# 40_Pin_Connector.net
KiCad netlist of a schematic drawn in Altium Designer
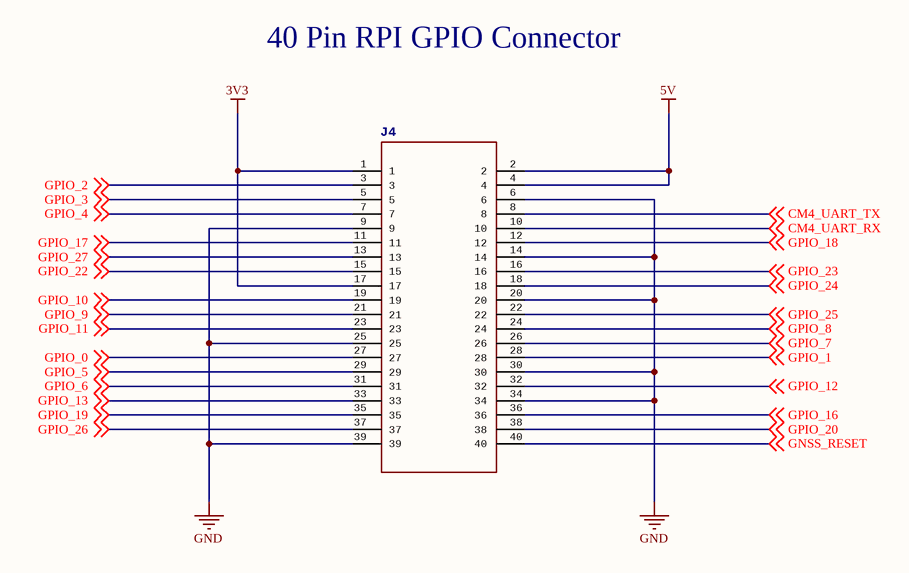
[diagram p0: 40_Pin_Connector.SchDoc]

(export (version "E")
  (design (tool "Eeschema 10.0.6"))
  (components
    (comp (ref "J4")
      (value "SAMTEC-A-HTSW-120-08-F-DJ")
      (footprint "SAMTEC-A-HTSW-120-08-F-D")
      (libsource (lib "SAMTEC-A-HTSW-120-08-F-D") (part "SAMTEC-A-HTSW-120-08-F-DJ"))
    )
  )
  (nets
    (net (code "1") (name "3V3") (class "Default")
      (node (ref "J4") (pin "1") (pinfunction "1_1") (pintype "passive"))
      (node (ref "J4") (pin "17") (pinfunction "17_17") (pintype "passive"))
    )
    (net (code "2") (name "5V") (class "Default")
      (node (ref "J4") (pin "2") (pinfunction "2_2") (pintype "passive"))
      (node (ref "J4") (pin "4") (pinfunction "4_4") (pintype "passive"))
    )
    (net (code "3") (name "CM4_UART_RX") (class "Default")
      (node (ref "J4") (pin "10") (pinfunction "10_10") (pintype "passive"))
    )
    (net (code "4") (name "CM4_UART_TX") (class "Default")
      (node (ref "J4") (pin "8") (pinfunction "8_8") (pintype "passive"))
    )
    (net (code "5") (name "GND") (class "Default")
      (node (ref "J4") (pin "14") (pinfunction "14_14") (pintype "passive"))
      (node (ref "J4") (pin "20") (pinfunction "20_20") (pintype "passive"))
      (node (ref "J4") (pin "25") (pinfunction "25_25") (pintype "passive"))
      (node (ref "J4") (pin "30") (pinfunction "30_30") (pintype "passive"))
      (node (ref "J4") (pin "34") (pinfunction "34_34") (pintype "passive"))
      (node (ref "J4") (pin "39") (pinfunction "39_39") (pintype "passive"))
      (node (ref "J4") (pin "6") (pinfunction "6_6") (pintype "passive"))
      (node (ref "J4") (pin "9") (pinfunction "9_9") (pintype "passive"))
    )
    (net (code "6") (name "GNSS_RESET") (class "Default")
      (node (ref "J4") (pin "40") (pinfunction "40_40") (pintype "passive"))
    )
    (net (code "7") (name "GPIO_0") (class "Default")
      (node (ref "J4") (pin "27") (pinfunction "27_27") (pintype "passive"))
    )
    (net (code "8") (name "GPIO_1") (class "Default")
      (node (ref "J4") (pin "28") (pinfunction "28_28") (pintype "passive"))
    )
    (net (code "9") (name "GPIO_2") (class "Default")
      (node (ref "J4") (pin "3") (pinfunction "3_3") (pintype "passive"))
    )
    (net (code "10") (name "GPIO_3") (class "Default")
      (node (ref "J4") (pin "5") (pinfunction "5_5") (pintype "passive"))
    )
    (net (code "11") (name "GPIO_4") (class "Default")
      (node (ref "J4") (pin "7") (pinfunction "7_7") (pintype "passive"))
    )
    (net (code "12") (name "GPIO_5") (class "Default")
      (node (ref "J4") (pin "29") (pinfunction "29_29") (pintype "passive"))
    )
    (net (code "13") (name "GPIO_6") (class "Default")
      (node (ref "J4") (pin "31") (pinfunction "31_31") (pintype "passive"))
    )
    (net (code "14") (name "GPIO_7") (class "Default")
      (node (ref "J4") (pin "26") (pinfunction "26_26") (pintype "passive"))
    )
    (net (code "15") (name "GPIO_8") (class "Default")
      (node (ref "J4") (pin "24") (pinfunction "24_24") (pintype "passive"))
    )
    (net (code "16") (name "GPIO_9") (class "Default")
      (node (ref "J4") (pin "21") (pinfunction "21_21") (pintype "passive"))
    )
    (net (code "17") (name "GPIO_10") (class "Default")
      (node (ref "J4") (pin "19") (pinfunction "19_19") (pintype "passive"))
    )
    (net (code "18") (name "GPIO_11") (class "Default")
      (node (ref "J4") (pin "23") (pinfunction "23_23") (pintype "passive"))
    )
    (net (code "19") (name "GPIO_12") (class "Default")
      (node (ref "J4") (pin "32") (pinfunction "32_32") (pintype "passive"))
    )
    (net (code "20") (name "GPIO_13") (class "Default")
      (node (ref "J4") (pin "33") (pinfunction "33_33") (pintype "passive"))
    )
    (net (code "21") (name "GPIO_16") (class "Default")
      (node (ref "J4") (pin "36") (pinfunction "36_36") (pintype "passive"))
    )
    (net (code "22") (name "GPIO_17") (class "Default")
      (node (ref "J4") (pin "11") (pinfunction "11_11") (pintype "passive"))
    )
    (net (code "23") (name "GPIO_18") (class "Default")
      (node (ref "J4") (pin "12") (pinfunction "12_12") (pintype "passive"))
    )
    (net (code "24") (name "GPIO_19") (class "Default")
      (node (ref "J4") (pin "35") (pinfunction "35_35") (pintype "passive"))
    )
    (net (code "25") (name "GPIO_20") (class "Default")
      (node (ref "J4") (pin "38") (pinfunction "38_38") (pintype "passive"))
    )
    (net (code "26") (name "GPIO_22") (class "Default")
      (node (ref "J4") (pin "15") (pinfunction "15_15") (pintype "passive"))
    )
    (net (code "27") (name "GPIO_23") (class "Default")
      (node (ref "J4") (pin "16") (pinfunction "16_16") (pintype "passive"))
    )
    (net (code "28") (name "GPIO_24") (class "Default")
      (node (ref "J4") (pin "18") (pinfunction "18_18") (pintype "passive"))
    )
    (net (code "29") (name "GPIO_25") (class "Default")
      (node (ref "J4") (pin "22") (pinfunction "22_22") (pintype "passive"))
    )
    (net (code "30") (name "GPIO_26") (class "Default")
      (node (ref "J4") (pin "37") (pinfunction "37_37") (pintype "passive"))
    )
    (net (code "31") (name "GPIO_27") (class "Default")
      (node (ref "J4") (pin "13") (pinfunction "13_13") (pintype "passive"))
    )
  )
)
